# Hierarchal-Power.net
KiCad netlist of a schematic drawn in Altium Designer
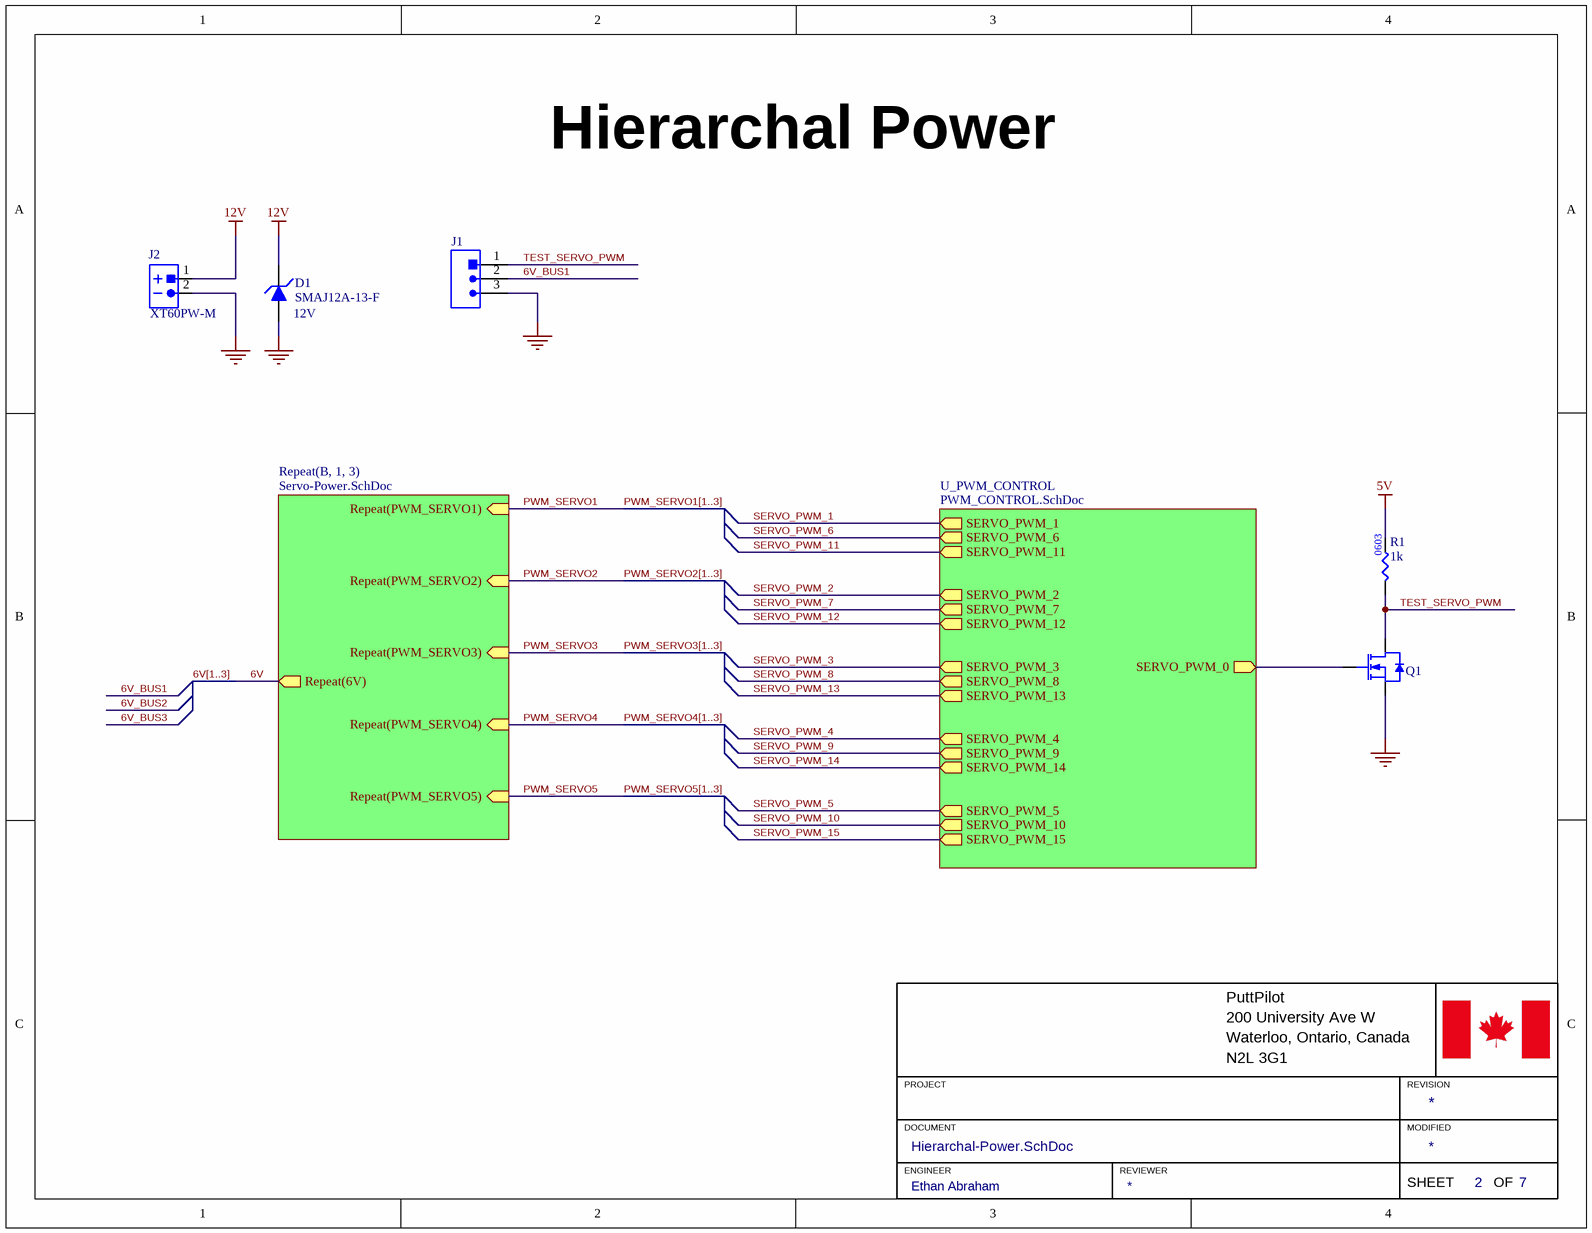
[diagram p0: Hierarchal-Power.SchDoc]

(export (version "E")
  (design (tool "Eeschema 10.0.6"))
  (components
    (comp (ref "D1")
      (value "SMAJ12A-13-F")
      (footprint "SMAJ12A-13-F")
      (description "TVS DIODE 12VWM")
      (fields (field (name "MANUFACTURER") "Diodes") (field (name "REP PK REVERSE VOLTAGE-MAX") "12V"))
      (libsource (lib "PuttPilot") (part "SMAJ12A-13-F"))
    )
    (comp (ref "J1")
      (value "TSW-101-08-G-T-RA")
      (footprint "HEADER_3POS_R/A_2.54MM")
      (description "CONN HEADER R/A 3POS 2.54MM")
      (libsource (lib "PuttPilot") (part "TSW-101-08-G-T-RA"))
    )
    (comp (ref "J2")
      (value "XT60PW-M")
      (footprint "XT60PW-M")
      (description "XT60PW Male")
      (fields (field (name "MANUFACTURER") "Unclassified"))
      (libsource (lib "PuttPilot") (part "XT60PW-M"))
    )
    (comp (ref "Q1")
      (value "DMN6140L-7")
      (footprint ".SOT-23-3")
      (description "MOSFET N-CH 60V 1.6A SOT-23")
      (fields (field (name "MANUFACTURER") "Diodes"))
      (libsource (lib "PuttPilot") (part "DMN6140L-7"))
    )
    (comp (ref "R1")
      (value "RC0603FR-071KL")
      (footprint ".RES_0603")
      (description "RES 1K OHM 0603")
      (fields
        (field (name "MANUFACTURER") "Yageo")
        (field (name "TOLERANCE") "1%")
        (field (name "RESISTANCE") "1k")
      )
      (libsource (lib "PuttPilot") (part "RC0603FR-071KL"))
    )
  )
  (nets
    (net (code "6") (name "/6V_BUS1") (class "Default")
      (node (ref "J1") (pin "2") (pinfunction "2_2") (pintype "passive"))
    )
    (net (code "14") (name "/SERVO_PWM_0") (class "Default")
      (node (ref "Q1") (pin "1") (pinfunction "Gate_1") (pintype "passive"))
    )
    (net (code "30") (name "/TEST_SERVO_PWM") (class "Default")
      (node (ref "J1") (pin "1") (pinfunction "1_1") (pintype "passive"))
      (node (ref "Q1") (pin "3") (pinfunction "Drain_3") (pintype "passive"))
      (node (ref "R1") (pin "1") (pinfunction "1_1") (pintype "passive"))
    )
    (net (code "31") (name "5V") (class "Default")
      (node (ref "R1") (pin "2") (pinfunction "2_2") (pintype "passive"))
    )
    (net (code "32") (name "12V") (class "Default")
      (node (ref "D1") (pin "2") (pinfunction "Pin_2_2") (pintype "passive"))
      (node (ref "J2") (pin "1") (pinfunction "1_1") (pintype "passive"))
    )
    (net (code "33") (name "GND") (class "Default")
      (node (ref "D1") (pin "1") (pinfunction "Pin_1_1") (pintype "passive"))
      (node (ref "J1") (pin "3") (pinfunction "3_3") (pintype "passive"))
      (node (ref "J2") (pin "2") (pinfunction "2_2") (pintype "passive"))
      (node (ref "Q1") (pin "2") (pinfunction "Source_2") (pintype "passive"))
    )
  )
)
